# gerbang_fix2.net
KiCad netlist of a schematic drawn in EAGLE
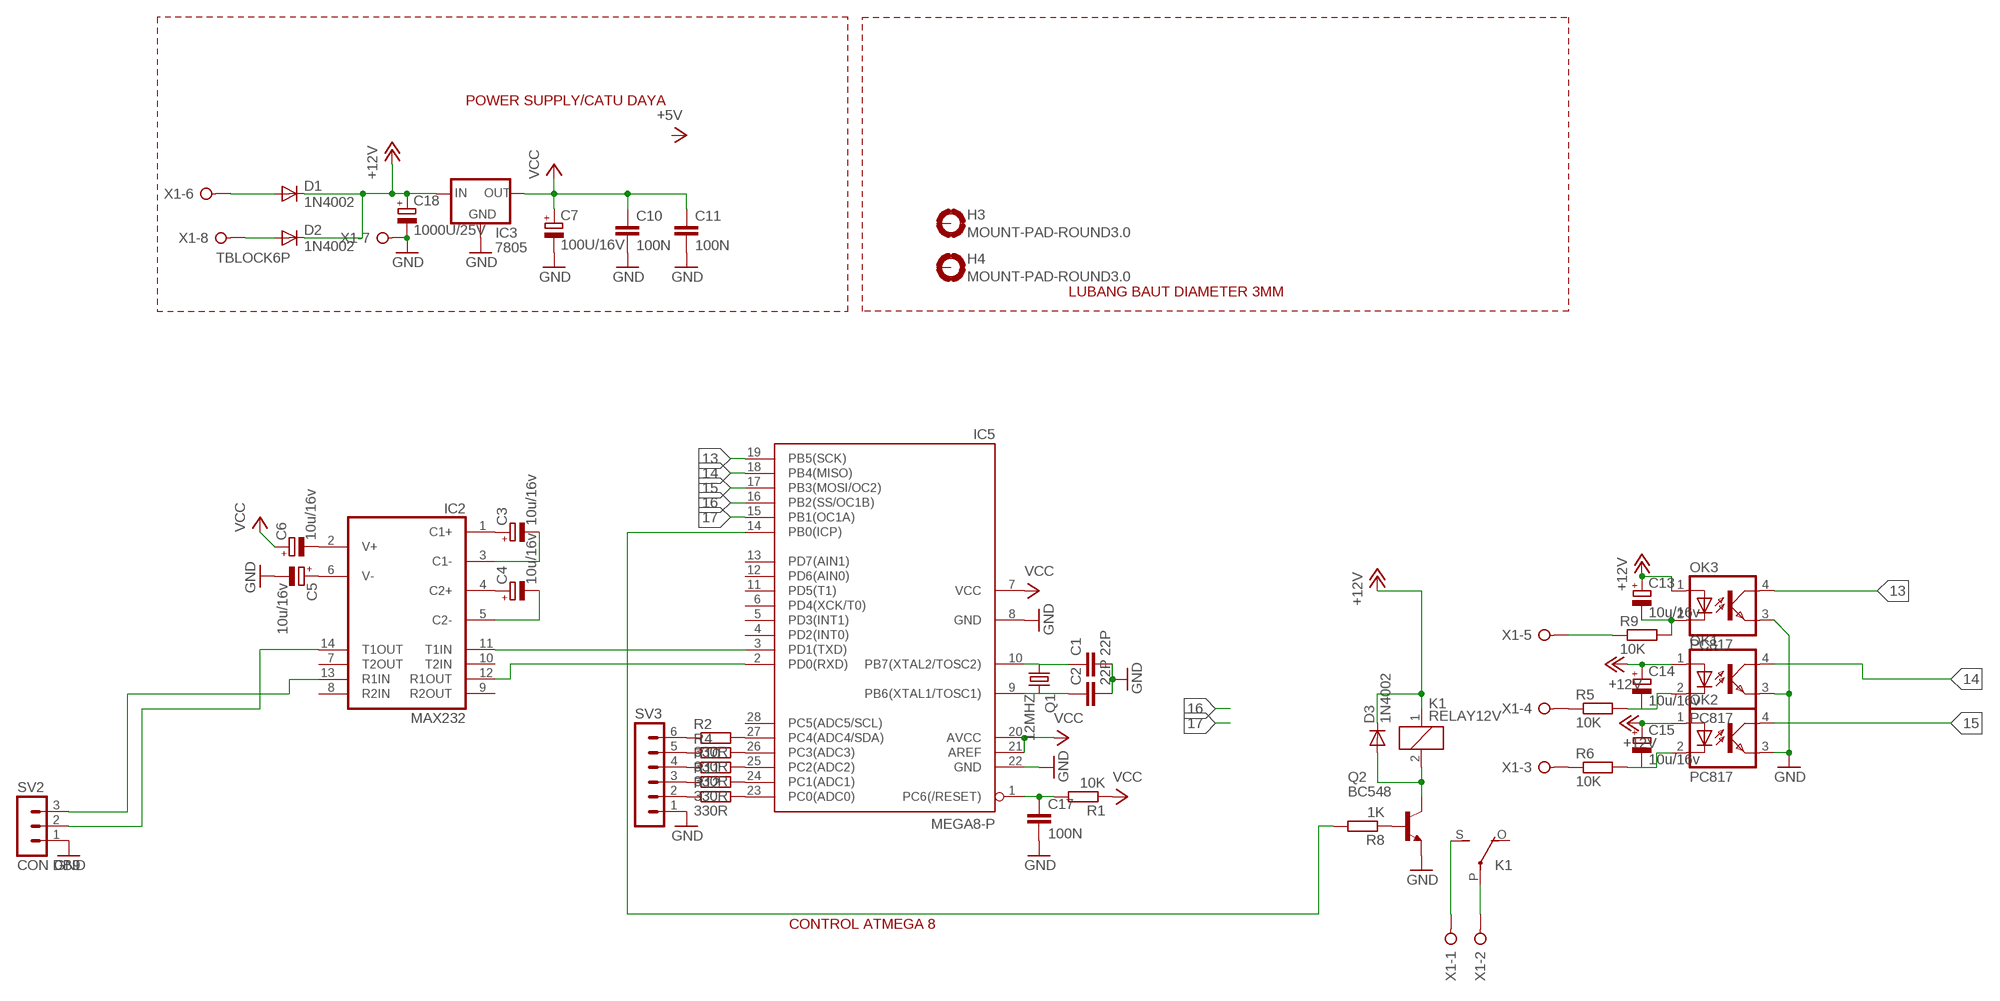
[diagram p0: schematic, sheet 1]

(export (version "E")
  (design (tool "Eeschema 10.0.6"))
  (components
    (comp (ref "C1")
      (value "22P")
      (footprint "eagle-import:C025-025X050")
      (libsource (lib "eagle-import") (part "C-EU025-025X050"))
    )
    (comp (ref "C2")
      (value "22P")
      (footprint "eagle-import:C025-025X050")
      (libsource (lib "eagle-import") (part "C-EU025-025X050"))
    )
    (comp (ref "C3")
      (value "10u/16v")
      (footprint "eagle-import:E2,5-6")
      (libsource (lib "eagle-import") (part "resistor_CPOL-EUE2.5-6"))
    )
    (comp (ref "C4")
      (value "10u/16v")
      (footprint "eagle-import:E2,5-6")
      (libsource (lib "eagle-import") (part "resistor_CPOL-EUE2.5-6"))
    )
    (comp (ref "C5")
      (value "10u/16v")
      (footprint "eagle-import:E2,5-6")
      (libsource (lib "eagle-import") (part "resistor_CPOL-EUE2.5-6"))
    )
    (comp (ref "C6")
      (value "10u/16v")
      (footprint "eagle-import:E2,5-6")
      (libsource (lib "eagle-import") (part "resistor_CPOL-EUE2.5-6"))
    )
    (comp (ref "C7")
      (value "100U/16V")
      (footprint "eagle-import:E2,5-6")
      (libsource (lib "eagle-import") (part "resistor_CPOL-EUE2.5-6"))
    )
    (comp (ref "C10")
      (value "100N")
      (footprint "eagle-import:C025-025X050")
      (libsource (lib "eagle-import") (part "C-EU025-025X050"))
    )
    (comp (ref "C11")
      (value "100N")
      (footprint "eagle-import:C025-025X050")
      (libsource (lib "eagle-import") (part "C-EU025-025X050"))
    )
    (comp (ref "C13")
      (value "10u/16v")
      (footprint "eagle-import:E2,5-6")
      (libsource (lib "eagle-import") (part "resistor_CPOL-EUE2.5-6"))
    )
    (comp (ref "C14")
      (value "10u/16v")
      (footprint "eagle-import:E2,5-6")
      (libsource (lib "eagle-import") (part "resistor_CPOL-EUE2.5-6"))
    )
    (comp (ref "C15")
      (value "10u/16v")
      (footprint "eagle-import:E2,5-6")
      (libsource (lib "eagle-import") (part "resistor_CPOL-EUE2.5-6"))
    )
    (comp (ref "C17")
      (value "100N")
      (footprint "eagle-import:C025-025X050")
      (libsource (lib "eagle-import") (part "C-EU025-025X050"))
    )
    (comp (ref "C18")
      (value "1000U/25V")
      (footprint "eagle-import:E5-8,5")
      (libsource (lib "eagle-import") (part "CPOL-EUE5-8.5"))
    )
    (comp (ref "D1")
      (value "1N4002")
      (footprint "eagle-import:DO35-10")
      (libsource (lib "eagle-import") (part "1N4148DO35-10"))
    )
    (comp (ref "D2")
      (value "1N4002")
      (footprint "eagle-import:DO35-10")
      (libsource (lib "eagle-import") (part "1N4148DO35-10"))
    )
    (comp (ref "D3")
      (value "1N4002")
      (footprint "eagle-import:DO35-10")
      (libsource (lib "eagle-import") (part "1N4148DO35-10"))
    )
    (comp (ref "H3")
      (value "MOUNT-PAD-ROUND3.0")
      (footprint "eagle-import:3,0-PAD")
      (libsource (lib "eagle-import") (part "MOUNT-PAD-ROUND3.0"))
    )
    (comp (ref "H4")
      (value "MOUNT-PAD-ROUND3.0")
      (footprint "eagle-import:3,0-PAD")
      (libsource (lib "eagle-import") (part "MOUNT-PAD-ROUND3.0"))
    )
    (comp (ref "IC2")
      (value "MAX232")
      (footprint "eagle-import:DIL16")
      (fields (field (name "MF") "MAXIM") (field (name "MPN") "MAX232ACPE+"))
      (libsource (lib "eagle-import") (part "MAX232"))
    )
    (comp (ref "IC3")
      (value "7805")
      (footprint "eagle-import:78XXS")
      (libsource (lib "eagle-import") (part "78XXS"))
    )
    (comp (ref "IC5")
      (value "MEGA8-P")
      (footprint "eagle-import:DIL28-3")
      (libsource (lib "eagle-import") (part "MEGA8-P"))
    )
    (comp (ref "K1")
      (value "RELAY12V")
      (footprint "eagle-import:ZF112")
      (libsource (lib "eagle-import") (part "ZF112"))
    )
    (comp (ref "OK1")
      (value "PC817")
      (footprint "eagle-import:DIL04")
      (fields (field (name "MPN") "PC817X4J000F"))
      (libsource (lib "eagle-import") (part "PC817"))
    )
    (comp (ref "OK2")
      (value "PC817")
      (footprint "eagle-import:DIL04")
      (fields (field (name "MPN") "PC817X4J000F"))
      (libsource (lib "eagle-import") (part "PC817"))
    )
    (comp (ref "OK3")
      (value "PC817")
      (footprint "eagle-import:DIL04")
      (fields (field (name "MPN") "PC817X4J000F"))
      (libsource (lib "eagle-import") (part "PC817"))
    )
    (comp (ref "Q1")
      (value "12MHZ")
      (footprint "eagle-import:HC49U-V")
      (libsource (lib "eagle-import") (part "CRYSTALHC49U-V"))
    )
    (comp (ref "Q2")
      (value "BC548")
      (footprint "eagle-import:TO92-EBC")
      (libsource (lib "eagle-import") (part "BC548"))
    )
    (comp (ref "R1")
      (value "10K")
      (footprint "eagle-import:0207_10")
      (libsource (lib "eagle-import") (part "resistor_R-EU_0207/10"))
    )
    (comp (ref "R2")
      (value "330R")
      (footprint "eagle-import:0204V")
      (libsource (lib "eagle-import") (part "R-EU_0204/2V"))
    )
    (comp (ref "R4")
      (value "330R")
      (footprint "eagle-import:0204V")
      (libsource (lib "eagle-import") (part "R-EU_0204/2V"))
    )
    (comp (ref "R5")
      (value "10K")
      (footprint "eagle-import:0204V")
      (libsource (lib "eagle-import") (part "R-EU_0204/2V"))
    )
    (comp (ref "R6")
      (value "10K")
      (footprint "eagle-import:0204V")
      (libsource (lib "eagle-import") (part "R-EU_0204/2V"))
    )
    (comp (ref "R8")
      (value "1K")
      (footprint "eagle-import:0207_10")
      (libsource (lib "eagle-import") (part "resistor_R-EU_0207/10"))
    )
    (comp (ref "R9")
      (value "10K")
      (footprint "eagle-import:0204V")
      (libsource (lib "eagle-import") (part "R-EU_0204/2V"))
    )
    (comp (ref "R10")
      (value "330R")
      (footprint "eagle-import:0204V")
      (libsource (lib "eagle-import") (part "R-EU_0204/2V"))
    )
    (comp (ref "R11")
      (value "330R")
      (footprint "eagle-import:0204V")
      (libsource (lib "eagle-import") (part "R-EU_0204/2V"))
    )
    (comp (ref "R12")
      (value "330R")
      (footprint "eagle-import:0204V")
      (libsource (lib "eagle-import") (part "R-EU_0204/2V"))
    )
    (comp (ref "SV2")
      (value "CON DB9")
      (footprint "eagle-import:MA03-1")
      (libsource (lib "eagle-import") (part "MA03-1"))
    )
    (comp (ref "SV3")
      (value "MA06-1")
      (footprint "eagle-import:MA06-1")
      (libsource (lib "eagle-import") (part "MA06-1"))
    )
    (comp (ref "X1")
      (value "TBLOCK6P")
      (footprint "eagle-import:W237-8P")
      (libsource (lib "eagle-import") (part "W237-08P"))
    )
  )
  (nets
    (net (code "2") (name "+12V") (class "Default")
      (node (ref "C13") (pin "+") (pinfunction "+_+") (pintype "passive"))
      (node (ref "C14") (pin "+") (pinfunction "+_+") (pintype "passive"))
      (node (ref "C15") (pin "+") (pinfunction "+_+") (pintype "passive"))
      (node (ref "C18") (pin "+") (pinfunction "+_+") (pintype "passive"))
      (node (ref "D1") (pin "C") (pinfunction "C_C") (pintype "passive"))
      (node (ref "D2") (pin "C") (pinfunction "C_C") (pintype "passive"))
      (node (ref "D3") (pin "C") (pinfunction "C_C") (pintype "passive"))
      (node (ref "IC3") (pin "IN") (pinfunction "IN_IN") (pintype "input"))
      (node (ref "K1") (pin "1") (pinfunction "1_1") (pintype "passive"))
      (node (ref "OK1") (pin "1") (pinfunction "A_1") (pintype "passive"))
      (node (ref "OK2") (pin "1") (pinfunction "A_1") (pintype "passive"))
      (node (ref "OK3") (pin "1") (pinfunction "A_1") (pintype "passive"))
    )
    (net (code "3") (name "13") (class "Default")
      (node (ref "IC5") (pin "19") (pinfunction "PB5(SCK)_19") (pintype "bidirectional"))
      (node (ref "OK3") (pin "4") (pinfunction "COL_4") (pintype "passive"))
    )
    (net (code "4") (name "14") (class "Default")
      (node (ref "IC5") (pin "18") (pinfunction "PB4(MISO)_18") (pintype "bidirectional"))
      (node (ref "OK1") (pin "4") (pinfunction "COL_4") (pintype "passive"))
    )
    (net (code "5") (name "15") (class "Default")
      (node (ref "IC5") (pin "17") (pinfunction "PB3(MOSI/OC2)_17") (pintype "bidirectional"))
      (node (ref "OK2") (pin "4") (pinfunction "COL_4") (pintype "passive"))
    )
    (net (code "6") (name "16") (class "Default")
      (node (ref "IC5") (pin "16") (pinfunction "PB2(SS/OC1B)_16") (pintype "bidirectional"))
    )
    (net (code "7") (name "17") (class "Default")
      (node (ref "IC5") (pin "15") (pinfunction "PB1(OC1A)_15") (pintype "bidirectional"))
    )
    (net (code "8") (name "GND") (class "Default")
      (node (ref "C1") (pin "2") (pinfunction "2_2") (pintype "passive"))
      (node (ref "C10") (pin "2") (pinfunction "2_2") (pintype "passive"))
      (node (ref "C11") (pin "2") (pinfunction "2_2") (pintype "passive"))
      (node (ref "C17") (pin "2") (pinfunction "2_2") (pintype "passive"))
      (node (ref "C18") (pin "-") (pinfunction "-_-") (pintype "passive"))
      (node (ref "C2") (pin "2") (pinfunction "2_2") (pintype "passive"))
      (node (ref "C5") (pin "-") (pinfunction "-_-") (pintype "passive"))
      (node (ref "C7") (pin "-") (pinfunction "-_-") (pintype "passive"))
      (node (ref "IC3") (pin "GND") (pinfunction "GND_GND") (pintype "input"))
      (node (ref "IC5") (pin "22") (pinfunction "GND_22") (pintype "power_in"))
      (node (ref "IC5") (pin "8") (pinfunction "GND_8") (pintype "power_in"))
      (node (ref "OK1") (pin "3") (pinfunction "EMIT_3") (pintype "passive"))
      (node (ref "OK2") (pin "3") (pinfunction "EMIT_3") (pintype "passive"))
      (node (ref "OK3") (pin "3") (pinfunction "EMIT_3") (pintype "passive"))
      (node (ref "Q2") (pin "E") (pinfunction "E_E") (pintype "passive"))
      (node (ref "SV2") (pin "1") (pinfunction "1_1") (pintype "passive"))
      (node (ref "SV3") (pin "1") (pinfunction "1_1") (pintype "passive"))
      (node (ref "X1") (pin "7") (pinfunction "KL_7") (pintype "passive"))
    )
    (net (code "9") (name "Net-(D3-PadA)") (class "Default")
      (node (ref "D3") (pin "A") (pinfunction "A_A") (pintype "passive"))
      (node (ref "K1") (pin "2") (pinfunction "2_2") (pintype "passive"))
      (node (ref "Q2") (pin "C") (pinfunction "C_C") (pintype "passive"))
    )
    (net (code "10") (name "Net-(IC2A-C1+)") (class "Default")
      (node (ref "C3") (pin "+") (pinfunction "+_+") (pintype "passive"))
      (node (ref "IC2") (pin "1") (pinfunction "C1+_1") (pintype "bidirectional"))
    )
    (net (code "11") (name "Net-(IC2A-C1-)") (class "Default")
      (node (ref "C3") (pin "-") (pinfunction "-_-") (pintype "passive"))
      (node (ref "IC2") (pin "3") (pinfunction "C1-_3") (pintype "bidirectional"))
    )
    (net (code "12") (name "Net-(IC2A-C2+)") (class "Default")
      (node (ref "C4") (pin "+") (pinfunction "+_+") (pintype "passive"))
      (node (ref "IC2") (pin "4") (pinfunction "C2+_4") (pintype "bidirectional"))
    )
    (net (code "13") (name "Net-(IC2A-C2-)") (class "Default")
      (node (ref "C4") (pin "-") (pinfunction "-_-") (pintype "passive"))
      (node (ref "IC2") (pin "5") (pinfunction "C2-_5") (pintype "bidirectional"))
    )
    (net (code "14") (name "Net-(IC2A-R1IN)") (class "Default")
      (node (ref "IC2") (pin "13") (pinfunction "R1IN_13") (pintype "input"))
      (node (ref "SV2") (pin "3") (pinfunction "3_3") (pintype "passive"))
    )
    (net (code "15") (name "Net-(IC2A-R1OUT)") (class "Default")
      (node (ref "IC2") (pin "12") (pinfunction "R1OUT_12") (pintype "output"))
      (node (ref "IC5") (pin "2") (pinfunction "PD0(RXD)_2") (pintype "bidirectional"))
    )
    (net (code "16") (name "Net-(IC2A-T1IN)") (class "Default")
      (node (ref "IC2") (pin "11") (pinfunction "T1IN_11") (pintype "input"))
      (node (ref "IC5") (pin "3") (pinfunction "PD1(TXD)_3") (pintype "bidirectional"))
    )
    (net (code "17") (name "Net-(IC2A-T1OUT)") (class "Default")
      (node (ref "IC2") (pin "14") (pinfunction "T1OUT_14") (pintype "output"))
      (node (ref "SV2") (pin "2") (pinfunction "2_2") (pintype "passive"))
    )
    (net (code "18") (name "Net-(IC2A-V+)") (class "Default")
      (node (ref "C6") (pin "-") (pinfunction "-_-") (pintype "passive"))
      (node (ref "IC2") (pin "2") (pinfunction "V+_2") (pintype "bidirectional"))
    )
    (net (code "19") (name "Net-(IC2A-V-)") (class "Default")
      (node (ref "C5") (pin "+") (pinfunction "+_+") (pintype "passive"))
      (node (ref "IC2") (pin "6") (pinfunction "V-_6") (pintype "bidirectional"))
    )
    (net (code "20") (name "Net-(IC5-PB0(ICP))") (class "Default")
      (node (ref "IC5") (pin "14") (pinfunction "PB0(ICP)_14") (pintype "bidirectional"))
      (node (ref "R8") (pin "2") (pinfunction "2_2") (pintype "passive"))
    )
    (net (code "21") (name "Net-(IC5-PB6(XTAL1{slash}TOSC1))") (class "Default")
      (node (ref "C2") (pin "1") (pinfunction "1_1") (pintype "passive"))
      (node (ref "IC5") (pin "9") (pinfunction "PB6(XTAL1/TOSC1)_9") (pintype "bidirectional"))
      (node (ref "Q1") (pin "2") (pinfunction "2_2") (pintype "passive"))
    )
    (net (code "22") (name "Net-(IC5-PB7(XTAL2{slash}TOSC2))") (class "Default")
      (node (ref "C1") (pin "1") (pinfunction "1_1") (pintype "passive"))
      (node (ref "IC5") (pin "10") (pinfunction "PB7(XTAL2/TOSC2)_10") (pintype "bidirectional"))
      (node (ref "Q1") (pin "1") (pinfunction "1_1") (pintype "passive"))
    )
    (net (code "23") (name "Net-(IC5-PC0(ADC0))") (class "Default")
      (node (ref "IC5") (pin "23") (pinfunction "PC0(ADC0)_23") (pintype "bidirectional"))
      (node (ref "R12") (pin "2") (pinfunction "2_2") (pintype "passive"))
    )
    (net (code "24") (name "Net-(IC5-PC1(ADC1))") (class "Default")
      (node (ref "IC5") (pin "24") (pinfunction "PC1(ADC1)_24") (pintype "bidirectional"))
      (node (ref "R11") (pin "2") (pinfunction "2_2") (pintype "passive"))
    )
    (net (code "25") (name "Net-(IC5-PC2(ADC2))") (class "Default")
      (node (ref "IC5") (pin "25") (pinfunction "PC2(ADC2)_25") (pintype "bidirectional"))
      (node (ref "R10") (pin "2") (pinfunction "2_2") (pintype "passive"))
    )
    (net (code "26") (name "Net-(IC5-PC3(ADC3))") (class "Default")
      (node (ref "IC5") (pin "26") (pinfunction "PC3(ADC3)_26") (pintype "bidirectional"))
      (node (ref "R4") (pin "2") (pinfunction "2_2") (pintype "passive"))
    )
    (net (code "27") (name "Net-(IC5-PC4(ADC4{slash}SDA))") (class "Default")
      (node (ref "IC5") (pin "27") (pinfunction "PC4(ADC4/SDA)_27") (pintype "bidirectional"))
      (node (ref "R2") (pin "2") (pinfunction "2_2") (pintype "passive"))
    )
    (net (code "28") (name "Net-(IC5-PC6({slash}RESET))") (class "Default")
      (node (ref "C17") (pin "1") (pinfunction "1_1") (pintype "passive"))
      (node (ref "IC5") (pin "1") (pinfunction "PC6(/RESET)_1") (pintype "bidirectional"))
      (node (ref "R1") (pin "2") (pinfunction "2_2") (pintype "passive"))
    )
    (net (code "29") (name "Net-(OK1-C)") (class "Default")
      (node (ref "C14") (pin "-") (pinfunction "-_-") (pintype "passive"))
      (node (ref "OK1") (pin "2") (pinfunction "C_2") (pintype "passive"))
      (node (ref "R5") (pin "2") (pinfunction "2_2") (pintype "passive"))
    )
    (net (code "30") (name "Net-(OK2-C)") (class "Default")
      (node (ref "C15") (pin "-") (pinfunction "-_-") (pintype "passive"))
      (node (ref "OK2") (pin "2") (pinfunction "C_2") (pintype "passive"))
      (node (ref "R6") (pin "2") (pinfunction "2_2") (pintype "passive"))
    )
    (net (code "31") (name "Net-(OK3-C)") (class "Default")
      (node (ref "C13") (pin "-") (pinfunction "-_-") (pintype "passive"))
      (node (ref "OK3") (pin "2") (pinfunction "C_2") (pintype "passive"))
      (node (ref "R9") (pin "2") (pinfunction "2_2") (pintype "passive"))
    )
    (net (code "32") (name "Net-(Q2-PadB)") (class "Default")
      (node (ref "Q2") (pin "B") (pinfunction "B_B") (pintype "passive"))
      (node (ref "R8") (pin "1") (pinfunction "1_1") (pintype "passive"))
    )
    (net (code "33") (name "Net-(R2-Pad1)") (class "Default")
      (node (ref "R2") (pin "1") (pinfunction "1_1") (pintype "passive"))
      (node (ref "SV3") (pin "6") (pinfunction "6_6") (pintype "passive"))
    )
    (net (code "34") (name "Net-(R4-Pad1)") (class "Default")
      (node (ref "R4") (pin "1") (pinfunction "1_1") (pintype "passive"))
      (node (ref "SV3") (pin "5") (pinfunction "5_5") (pintype "passive"))
    )
    (net (code "35") (name "Net-(R10-Pad1)") (class "Default")
      (node (ref "R10") (pin "1") (pinfunction "1_1") (pintype "passive"))
      (node (ref "SV3") (pin "4") (pinfunction "4_4") (pintype "passive"))
    )
    (net (code "36") (name "Net-(R11-Pad1)") (class "Default")
      (node (ref "R11") (pin "1") (pinfunction "1_1") (pintype "passive"))
      (node (ref "SV3") (pin "3") (pinfunction "3_3") (pintype "passive"))
    )
    (net (code "37") (name "Net-(R12-Pad1)") (class "Default")
      (node (ref "R12") (pin "1") (pinfunction "1_1") (pintype "passive"))
      (node (ref "SV3") (pin "2") (pinfunction "2_2") (pintype "passive"))
    )
    (net (code "38") (name "Net-(X1A-KL)") (class "Default")
      (node (ref "K1") (pin "S") (pinfunction "S_S") (pintype "passive"))
      (node (ref "X1") (pin "1") (pinfunction "KL_1") (pintype "passive"))
    )
    (net (code "39") (name "Net-(X1B-KL)") (class "Default")
      (node (ref "K1") (pin "P") (pinfunction "P_P") (pintype "passive"))
      (node (ref "X1") (pin "2") (pinfunction "KL_2") (pintype "passive"))
    )
    (net (code "40") (name "Net-(X1C-KL)") (class "Default")
      (node (ref "R6") (pin "1") (pinfunction "1_1") (pintype "passive"))
      (node (ref "X1") (pin "3") (pinfunction "KL_3") (pintype "passive"))
    )
    (net (code "41") (name "Net-(X1D-KL)") (class "Default")
      (node (ref "R5") (pin "1") (pinfunction "1_1") (pintype "passive"))
      (node (ref "X1") (pin "4") (pinfunction "KL_4") (pintype "passive"))
    )
    (net (code "42") (name "Net-(X1E-KL)") (class "Default")
      (node (ref "R9") (pin "1") (pinfunction "1_1") (pintype "passive"))
      (node (ref "X1") (pin "5") (pinfunction "KL_5") (pintype "passive"))
    )
    (net (code "43") (name "Net-(X1F-KL)") (class "Default")
      (node (ref "D1") (pin "A") (pinfunction "A_A") (pintype "passive"))
      (node (ref "X1") (pin "6") (pinfunction "KL_6") (pintype "passive"))
    )
    (net (code "44") (name "Net-(X1H-KL)") (class "Default")
      (node (ref "D2") (pin "A") (pinfunction "A_A") (pintype "passive"))
      (node (ref "X1") (pin "8") (pinfunction "KL_8") (pintype "passive"))
    )
    (net (code "45") (name "VCC") (class "Default")
      (node (ref "C10") (pin "1") (pinfunction "1_1") (pintype "passive"))
      (node (ref "C11") (pin "1") (pinfunction "1_1") (pintype "passive"))
      (node (ref "C6") (pin "+") (pinfunction "+_+") (pintype "passive"))
      (node (ref "C7") (pin "+") (pinfunction "+_+") (pintype "passive"))
      (node (ref "IC3") (pin "OUT") (pinfunction "OUT_OUT") (pintype "passive"))
      (node (ref "IC5") (pin "20") (pinfunction "AVCC_20") (pintype "power_in"))
      (node (ref "IC5") (pin "21") (pinfunction "AREF_21") (pintype "passive"))
      (node (ref "IC5") (pin "7") (pinfunction "VCC_7") (pintype "power_in"))
      (node (ref "R1") (pin "1") (pinfunction "1_1") (pintype "passive"))
    )
    (net (code "46") (name "unconnected-(H3-MOUNT-PadB3,0)") (class "Default")
      (node (ref "H3") (pin "B3,0") (pinfunction "MOUNT_B3,0") (pintype "passive"))
    )
    (net (code "47") (name "unconnected-(H4-MOUNT-PadB3,0)") (class "Default")
      (node (ref "H4") (pin "B3,0") (pinfunction "MOUNT_B3,0") (pintype "passive"))
    )
    (net (code "48") (name "unconnected-(IC2A-R2IN-Pad8)") (class "Default")
      (node (ref "IC2") (pin "8") (pinfunction "R2IN_8") (pintype "input"))
    )
    (net (code "49") (name "unconnected-(IC2A-R2OUT-Pad9)") (class "Default")
      (node (ref "IC2") (pin "9") (pinfunction "R2OUT_9") (pintype "output"))
    )
    (net (code "50") (name "unconnected-(IC2A-T2IN-Pad10)") (class "Default")
      (node (ref "IC2") (pin "10") (pinfunction "T2IN_10") (pintype "input"))
    )
    (net (code "51") (name "unconnected-(IC2A-T2OUT-Pad7)") (class "Default")
      (node (ref "IC2") (pin "7") (pinfunction "T2OUT_7") (pintype "output"))
    )
    (net (code "52") (name "unconnected-(IC5-PC5(ADC5{slash}SCL)-Pad28)") (class "Default")
      (node (ref "IC5") (pin "28") (pinfunction "PC5(ADC5/SCL)_28") (pintype "bidirectional"))
    )
    (net (code "53") (name "unconnected-(IC5-PD2(INT0)-Pad4)") (class "Default")
      (node (ref "IC5") (pin "4") (pinfunction "PD2(INT0)_4") (pintype "bidirectional"))
    )
    (net (code "54") (name "unconnected-(IC5-PD3(INT1)-Pad5)") (class "Default")
      (node (ref "IC5") (pin "5") (pinfunction "PD3(INT1)_5") (pintype "bidirectional"))
    )
    (net (code "55") (name "unconnected-(IC5-PD4(XCK{slash}T0)-Pad6)") (class "Default")
      (node (ref "IC5") (pin "6") (pinfunction "PD4(XCK/T0)_6") (pintype "bidirectional"))
    )
    (net (code "56") (name "unconnected-(IC5-PD5(T1)-Pad11)") (class "Default")
      (node (ref "IC5") (pin "11") (pinfunction "PD5(T1)_11") (pintype "bidirectional"))
    )
    (net (code "57") (name "unconnected-(IC5-PD6(AIN0)-Pad12)") (class "Default")
      (node (ref "IC5") (pin "12") (pinfunction "PD6(AIN0)_12") (pintype "bidirectional"))
    )
    (net (code "58") (name "unconnected-(IC5-PD7(AIN1)-Pad13)") (class "Default")
      (node (ref "IC5") (pin "13") (pinfunction "PD7(AIN1)_13") (pintype "bidirectional"))
    )
    (net (code "59") (name "unconnected-(K1-PadO)") (class "Default")
      (node (ref "K1") (pin "O") (pinfunction "O_O") (pintype "passive"))
    )
  )
)
